# MCU.net
KiCad netlist of a schematic drawn in Altium Designer
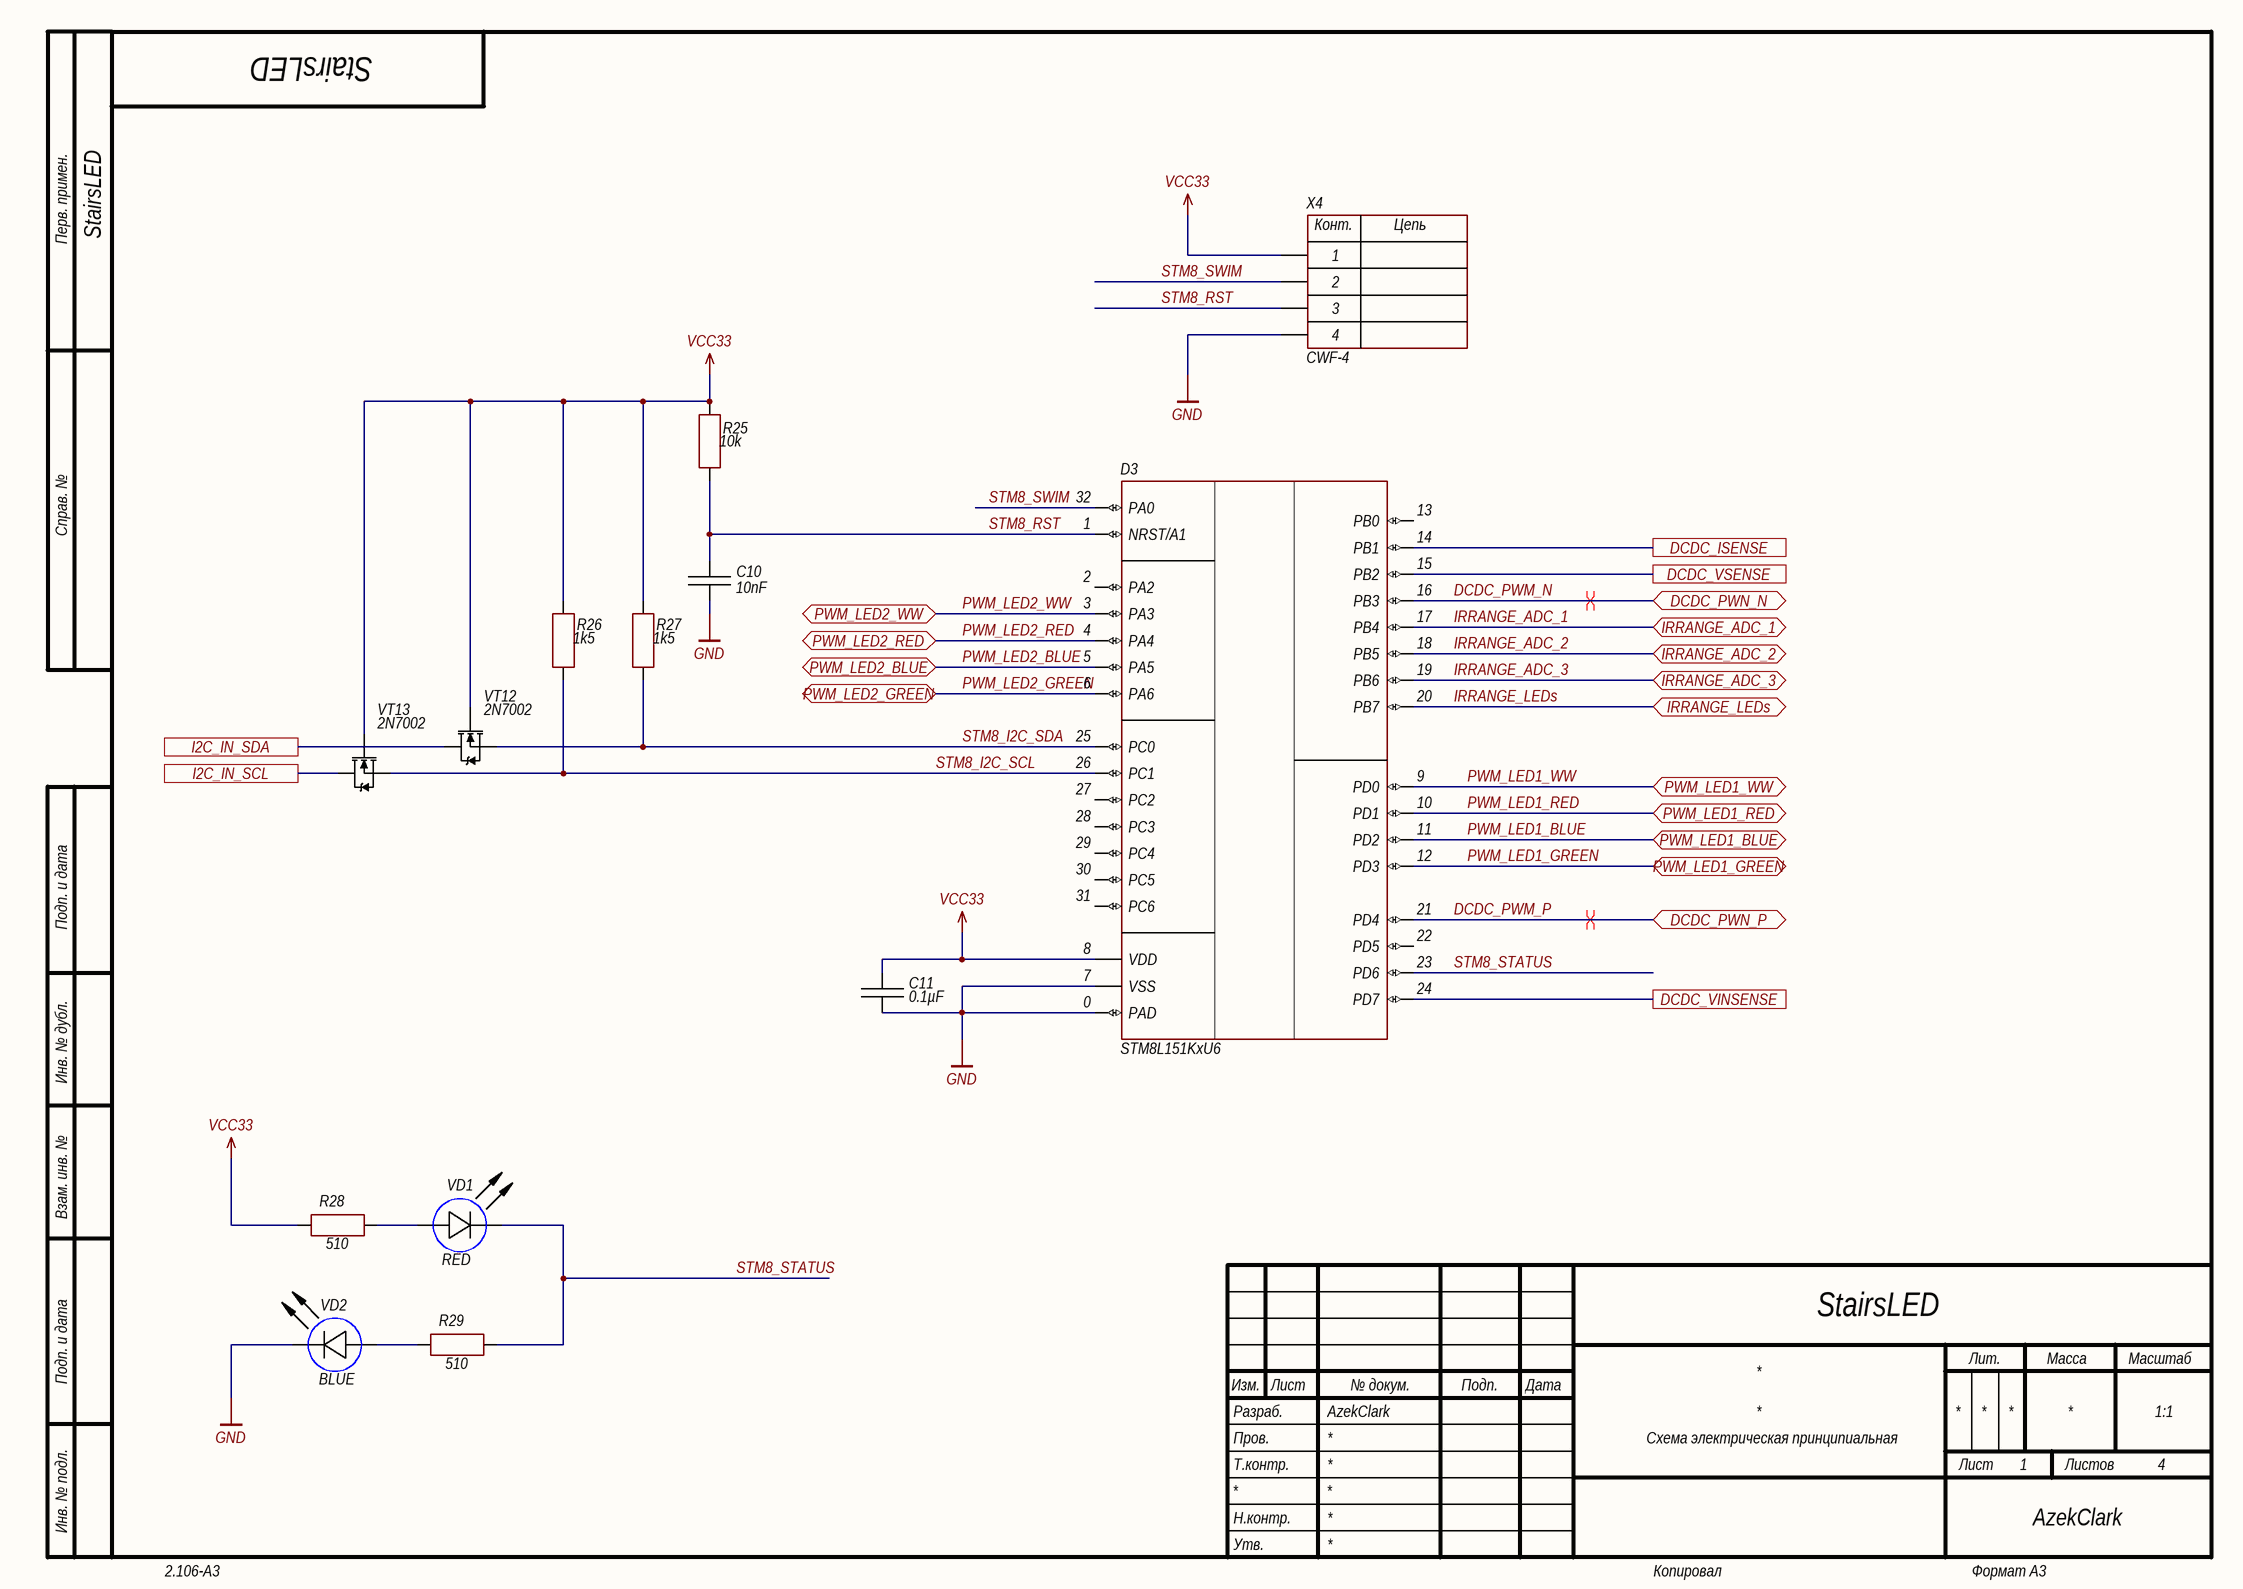
[diagram p0: MCU.SchDoc]

(export (version "E")
  (design (tool "Eeschema 10.0.6"))
  (components
    (comp (ref "C10") (value "10nF") (footprint "CH0603C") (libsource (lib "Discrete") (part "Capacitor")))
    (comp (ref "C11") (value "0.1µF") (footprint "CH0603C") (libsource (lib "Discrete") (part "Capacitor")))
    (comp (ref "D3")
      (value "STM8L151KxU6")
      (footprint "32-UFQFPN")
      (description "STM8")
      (fields (field (name "MANUFACTURER") "ST Microelectronics"))
      (libsource (lib "Digital") (part "STM8L151KxU6"))
    )
    (comp (ref "R25") (value "10k") (footprint "CH0603R") (libsource (lib "Discrete") (part "Resistor")))
    (comp (ref "R26") (value "1k5") (footprint "CH0603R") (libsource (lib "Discrete") (part "Resistor")))
    (comp (ref "R27") (value "1k5") (footprint "CH0603R") (libsource (lib "Discrete") (part "Resistor")))
    (comp (ref "R28") (value "510") (footprint "CH0603R") (libsource (lib "") (part "Resistor_1")))
    (comp (ref "R29") (value "510") (footprint "CH0603R") (libsource (lib "") (part "Resistor_1")))
    (comp (ref "VD1") (value "RED") (footprint "CH0603LR") (libsource (lib "Discrete") (part "LED")))
    (comp (ref "VD2") (value "BLUE") (footprint "CH0603LB") (libsource (lib "Discrete") (part "LED")))
    (comp (ref "VT12")
      (value "2N7002")
      (footprint "SOT23_132")
      (description "Mosfet")
      (fields (field (name "MANUFACTURER") "ON Semiconductor"))
      (libsource (lib "Transistor") (part "N-chanel"))
    )
    (comp (ref "VT13")
      (value "2N7002")
      (footprint "SOT23_132")
      (description "Mosfet")
      (fields (field (name "MANUFACTURER") "ON Semiconductor"))
      (libsource (lib "Transistor") (part "N-chanel"))
    )
    (comp (ref "X4")
      (value "CWF-4")
      (footprint "CON: CWF-4")
      (libsource (lib "Connectors") (part "4-Connector"))
    )
  )
  (nets
    (net (code "1") (name "/DCDC_ISENSE") (class "Default")
      (node (ref "D3") (pin "14") (pinfunction "PB1_14") (pintype "bidirectional"))
    )
    (net (code "2") (name "/DCDC_PWM_N") (class "Default")
      (node (ref "D3") (pin "16") (pinfunction "PB3_16") (pintype "bidirectional"))
    )
    (net (code "3") (name "/DCDC_PWM_P") (class "Default")
      (node (ref "D3") (pin "21") (pinfunction "PD4_21") (pintype "bidirectional"))
    )
    (net (code "4") (name "/DCDC_VINSENSE") (class "Default")
      (node (ref "D3") (pin "24") (pinfunction "PD7_24") (pintype "bidirectional"))
    )
    (net (code "5") (name "/DCDC_VSENSE") (class "Default")
      (node (ref "D3") (pin "15") (pinfunction "PB2_15") (pintype "bidirectional"))
    )
    (net (code "6") (name "/I2C_IN_SCL") (class "Default")
      (node (ref "VT13") (pin "2") (pinfunction "D_2") (pintype "passive"))
    )
    (net (code "7") (name "/I2C_IN_SDA") (class "Default")
      (node (ref "VT12") (pin "2") (pinfunction "D_2") (pintype "passive"))
    )
    (net (code "8") (name "/IRRANGE_ADC_1") (class "Default")
      (node (ref "D3") (pin "17") (pinfunction "PB4_17") (pintype "bidirectional"))
    )
    (net (code "9") (name "/IRRANGE_ADC_2") (class "Default")
      (node (ref "D3") (pin "18") (pinfunction "PB5_18") (pintype "bidirectional"))
    )
    (net (code "10") (name "/IRRANGE_ADC_3") (class "Default")
      (node (ref "D3") (pin "19") (pinfunction "PB6_19") (pintype "bidirectional"))
    )
    (net (code "11") (name "/IRRANGE_LEDs") (class "Default")
      (node (ref "D3") (pin "20") (pinfunction "PB7_20") (pintype "bidirectional"))
    )
    (net (code "12") (name "/PWM_LED1_BLUE") (class "Default")
      (node (ref "D3") (pin "11") (pinfunction "PD2_11") (pintype "bidirectional"))
    )
    (net (code "13") (name "/PWM_LED1_GREEN") (class "Default")
      (node (ref "D3") (pin "12") (pinfunction "PD3_12") (pintype "bidirectional"))
    )
    (net (code "14") (name "/PWM_LED1_RED") (class "Default")
      (node (ref "D3") (pin "10") (pinfunction "PD1_10") (pintype "bidirectional"))
    )
    (net (code "15") (name "/PWM_LED1_WW") (class "Default")
      (node (ref "D3") (pin "9") (pinfunction "PD0_9") (pintype "bidirectional"))
    )
    (net (code "16") (name "/PWM_LED2_BLUE") (class "Default")
      (node (ref "D3") (pin "5") (pinfunction "PA5_5") (pintype "bidirectional"))
    )
    (net (code "17") (name "/PWM_LED2_GREEN") (class "Default")
      (node (ref "D3") (pin "6") (pinfunction "PA6_6") (pintype "bidirectional"))
    )
    (net (code "18") (name "/PWM_LED2_RED") (class "Default")
      (node (ref "D3") (pin "4") (pinfunction "PA4_4") (pintype "bidirectional"))
    )
    (net (code "19") (name "/PWM_LED2_WW") (class "Default")
      (node (ref "D3") (pin "3") (pinfunction "PA3_3") (pintype "bidirectional"))
    )
    (net (code "20") (name "/STM8_I2C_SCL") (class "Default")
      (node (ref "D3") (pin "26") (pinfunction "PC1_26") (pintype "bidirectional"))
      (node (ref "R26") (pin "1") (pinfunction "1_1") (pintype "passive"))
      (node (ref "VT13") (pin "3") (pinfunction "S_3") (pintype "passive"))
    )
    (net (code "21") (name "/STM8_I2C_SDA") (class "Default")
      (node (ref "D3") (pin "25") (pinfunction "PC0_25") (pintype "bidirectional"))
      (node (ref "R27") (pin "1") (pinfunction "1_1") (pintype "passive"))
      (node (ref "VT12") (pin "3") (pinfunction "S_3") (pintype "passive"))
    )
    (net (code "22") (name "/STM8_RST") (class "Default")
      (node (ref "C10") (pin "2") (pinfunction "2_2") (pintype "power_in"))
      (node (ref "D3") (pin "1") (pinfunction "NRST/A1_1") (pintype "bidirectional"))
      (node (ref "R25") (pin "1") (pinfunction "1_1") (pintype "passive"))
      (node (ref "X4") (pin "3") (pinfunction "3_3") (pintype "power_in"))
    )
    (net (code "23") (name "/STM8_STATUS") (class "Default")
      (node (ref "D3") (pin "23") (pinfunction "PD6_23") (pintype "bidirectional"))
      (node (ref "R29") (pin "1") (pinfunction "1_1") (pintype "passive"))
      (node (ref "VD1") (pin "2") (pinfunction "C_2") (pintype "passive"))
    )
    (net (code "24") (name "/STM8_SWIM") (class "Default")
      (node (ref "D3") (pin "32") (pinfunction "PA0_32") (pintype "bidirectional"))
      (node (ref "X4") (pin "2") (pinfunction "2_2") (pintype "passive"))
    )
    (net (code "25") (name "GND") (class "Default")
      (node (ref "C10") (pin "1") (pinfunction "1_1") (pintype "power_in"))
      (node (ref "C11") (pin "2") (pinfunction "2_2") (pintype "power_in"))
      (node (ref "D3") (pin "0") (pinfunction "PAD_0") (pintype "bidirectional"))
      (node (ref "D3") (pin "7") (pinfunction "VSS_7") (pintype "power_in"))
      (node (ref "VD2") (pin "2") (pinfunction "C_2") (pintype "passive"))
      (node (ref "X4") (pin "4") (pinfunction "4_4") (pintype "power_in"))
    )
    (net (code "26") (name "Net-(VD1-A)") (class "Default")
      (node (ref "R28") (pin "1") (pinfunction "1_1") (pintype "passive"))
      (node (ref "VD1") (pin "1") (pinfunction "A_1") (pintype "passive"))
    )
    (net (code "27") (name "Net-(VD2-A)") (class "Default")
      (node (ref "R29") (pin "2") (pinfunction "2_2") (pintype "passive"))
      (node (ref "VD2") (pin "1") (pinfunction "A_1") (pintype "passive"))
    )
    (net (code "28") (name "VCC33") (class "Default")
      (node (ref "C11") (pin "1") (pinfunction "1_1") (pintype "power_in"))
      (node (ref "D3") (pin "8") (pinfunction "VDD_8") (pintype "power_in"))
      (node (ref "R25") (pin "2") (pinfunction "2_2") (pintype "passive"))
      (node (ref "R26") (pin "2") (pinfunction "2_2") (pintype "passive"))
      (node (ref "R27") (pin "2") (pinfunction "2_2") (pintype "passive"))
      (node (ref "R28") (pin "2") (pinfunction "2_2") (pintype "passive"))
      (node (ref "VT12") (pin "1") (pinfunction "G_1") (pintype "passive"))
      (node (ref "VT13") (pin "1") (pinfunction "G_1") (pintype "passive"))
      (node (ref "X4") (pin "1") (pinfunction "1_1") (pintype "passive"))
    )
    (net (code "29") (name "unconnected-(D3-PA2-Pad2)") (class "Default")
      (node (ref "D3") (pin "2") (pinfunction "PA2_2") (pintype "bidirectional"))
    )
    (net (code "30") (name "unconnected-(D3-PB0-Pad13)") (class "Default")
      (node (ref "D3") (pin "13") (pinfunction "PB0_13") (pintype "bidirectional"))
    )
    (net (code "31") (name "unconnected-(D3-PC2-Pad27)") (class "Default")
      (node (ref "D3") (pin "27") (pinfunction "PC2_27") (pintype "bidirectional"))
    )
    (net (code "32") (name "unconnected-(D3-PC3-Pad28)") (class "Default")
      (node (ref "D3") (pin "28") (pinfunction "PC3_28") (pintype "bidirectional"))
    )
    (net (code "33") (name "unconnected-(D3-PC4-Pad29)") (class "Default")
      (node (ref "D3") (pin "29") (pinfunction "PC4_29") (pintype "bidirectional"))
    )
    (net (code "34") (name "unconnected-(D3-PC5-Pad30)") (class "Default")
      (node (ref "D3") (pin "30") (pinfunction "PC5_30") (pintype "bidirectional"))
    )
    (net (code "35") (name "unconnected-(D3-PC6-Pad31)") (class "Default")
      (node (ref "D3") (pin "31") (pinfunction "PC6_31") (pintype "bidirectional"))
    )
    (net (code "36") (name "unconnected-(D3-PD5-Pad22)") (class "Default")
      (node (ref "D3") (pin "22") (pinfunction "PD5_22") (pintype "bidirectional"))
    )
  )
)
